# Support.net
KiCad netlist of a schematic drawn in Altium Designer
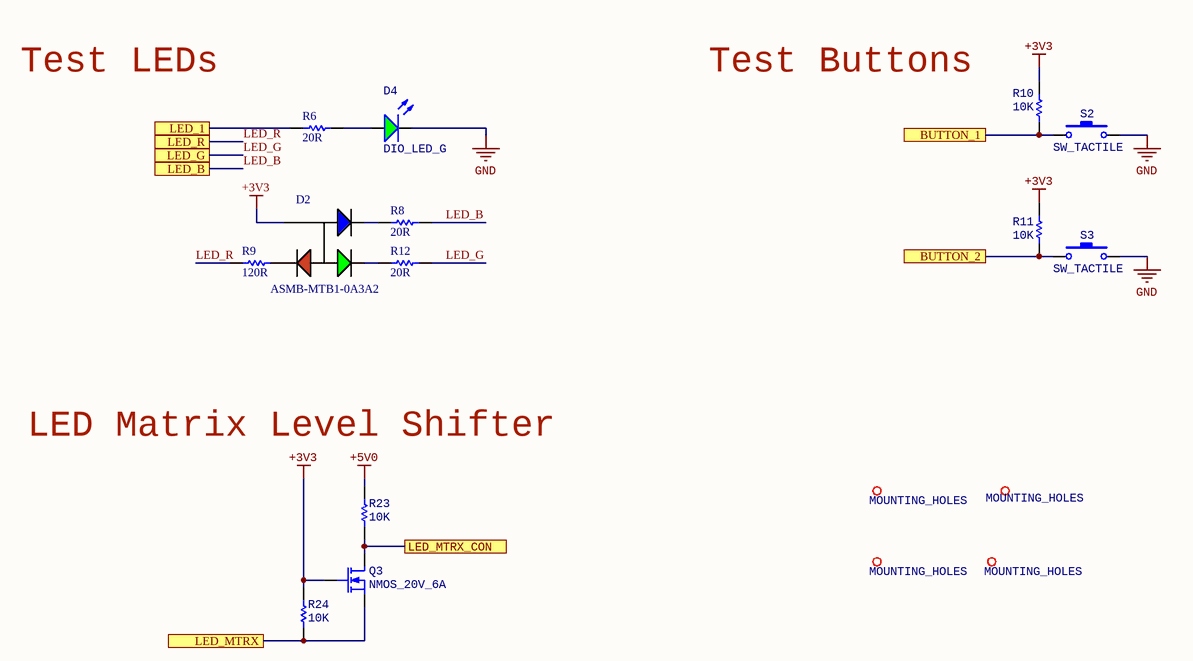
[diagram p0: Support.SchDoc]

(export (version "E")
  (design (tool "Eeschema 10.0.6"))
  (components
    (comp (ref "D2")
      (value "LED_RGB")
      (footprint "LED_RGB")
      (description "LED RGB DIFFUSED 4PLCC SMD")
      (fields (field (name "MANUFACTURER PART NUMBER 1") "ASMB-MTB1-0A3A2"))
      (libsource (lib "UWRT_Schematic_Library_2020") (part "LED_RGB"))
    )
    (comp (ref "D4")
      (value "DIO_LED_G")
      (footprint "LED_0805_LINE")
      (description "LED GREEN DIFFUSED 0805 SMD")
      (fields (field (name "MANUFACTURER") "OSRAM") (field (name "MPN") "LG R971-KN-1"))
      (libsource (lib "UWRT_Schematic_Library_2020") (part "DIO_LED_G"))
    )
    (comp (ref "MH1")
      (value "MOUNTING_HOLES")
      (footprint "MOUNTING_HOLE")
      (description "6cm x 6cm")
      (libsource (lib "UWRT_Schematic_Library_2020") (part "MOUNTING_HOLES"))
    )
    (comp (ref "MH2")
      (value "MOUNTING_HOLES")
      (footprint "MOUNTING_HOLE")
      (description "6cm x 6cm")
      (libsource (lib "UWRT_Schematic_Library_2020") (part "MOUNTING_HOLES"))
    )
    (comp (ref "MH3")
      (value "MOUNTING_HOLES")
      (footprint "MOUNTING_HOLE")
      (description "6cm x 6cm")
      (libsource (lib "UWRT_Schematic_Library_2020") (part "MOUNTING_HOLES"))
    )
    (comp (ref "MH4")
      (value "MOUNTING_HOLES")
      (footprint "MOUNTING_HOLE")
      (description "6cm x 6cm")
      (libsource (lib "UWRT_Schematic_Library_2020") (part "MOUNTING_HOLES"))
    )
    (comp (ref "Q3")
      (value "NMOS_20V_6A")
      (footprint "NMOS_SOT23-3")
      (description "MOSFET N-CH 20V 6A SOT23")
      (fields (field (name "MPN") "AO3420") (field (name "MANUFACTURER") "Alpha & Omega"))
      (libsource (lib "UWRT_Schematic_Library_2020") (part "NMOS_20V_6A"))
    )
    (comp (ref "R6")
      (value "20R")
      (footprint "RESC0603(1608)_N")
      (description "RES SMD 20 OHM 5% 1/10W 0603")
      (fields (field (name "MANUFACTURER") "Yageo") (field (name "MPN") "RC0603JR-0720RL"))
      (libsource (lib "UWRT_Schematic_Library_2020") (part "RES_20R_0603"))
    )
    (comp (ref "R8")
      (value "20R")
      (footprint "RESC0603(1608)_N")
      (description "RES SMD 20 OHM 5% 1/10W 0603")
      (fields (field (name "MANUFACTURER") "Yageo") (field (name "MPN") "RC0603JR-0720RL"))
      (libsource (lib "UWRT_Schematic_Library_2020") (part "RES_20R_0603"))
    )
    (comp (ref "R9")
      (value "120R")
      (footprint "RESC0603(1608)_N")
      (description "RES SMD 120 OHM 5% 1/10W 0603")
      (fields (field (name "MANUFACTURER") "Yageo") (field (name "MPN") "RC0603JR-07120RL"))
      (libsource (lib "UWRT_Schematic_Library_2020") (part "RES_120R_0603"))
    )
    (comp (ref "R10")
      (value "10K")
      (footprint "RESC0603(1608)_N")
      (description "RES SMD 10K OHM 5% 1/10W 0603")
      (fields (field (name "MANUFACTURER") "Yageo") (field (name "TOLERANCE") "5%"))
      (libsource (lib "UWRT_Schematic_Library_2020") (part "RES_10K_0603"))
    )
    (comp (ref "R11")
      (value "10K")
      (footprint "RESC0603(1608)_N")
      (description "RES SMD 10K OHM 5% 1/10W 0603")
      (fields (field (name "MANUFACTURER") "Yageo") (field (name "TOLERANCE") "5%"))
      (libsource (lib "UWRT_Schematic_Library_2020") (part "RES_10K_0603"))
    )
    (comp (ref "R12")
      (value "20R")
      (footprint "RESC0603(1608)_N")
      (description "RES SMD 20 OHM 5% 1/10W 0603")
      (fields (field (name "MANUFACTURER") "Yageo") (field (name "MPN") "RC0603JR-0720RL"))
      (libsource (lib "UWRT_Schematic_Library_2020") (part "RES_20R_0603"))
    )
    (comp (ref "R23")
      (value "10K")
      (footprint "RESC0603(1608)_N")
      (description "RES SMD 10K OHM 5% 1/10W 0603")
      (fields (field (name "MANUFACTURER") "Yageo") (field (name "MPN") "RC0603JR-0710KL"))
      (libsource (lib "UWRT_Schematic_Library_2020") (part "RES_10K_0603"))
    )
    (comp (ref "R24")
      (value "10K")
      (footprint "RESC0603(1608)_N")
      (description "RES SMD 10K OHM 5% 1/10W 0603")
      (fields (field (name "MANUFACTURER") "Yageo") (field (name "MPN") "RC0603JR-0710KL"))
      (libsource (lib "UWRT_Schematic_Library_2020") (part "RES_10K_0603"))
    )
    (comp (ref "S2")
      (value "SW_TACTILE")
      (footprint "B3U-1100P")
      (description "Tactile Switch (Grey)")
      (fields (field (name "MPN") "B3U-1100P") (field (name "MANUFACTURER") "Omron Electronics Inc-EMC Div"))
      (libsource (lib "UWRT_Schematic_Library_2020") (part "SW_TACTILE"))
    )
    (comp (ref "S3")
      (value "SW_TACTILE")
      (footprint "B3U-1100P")
      (description "Tactile Switch (Grey)")
      (fields (field (name "MPN") "B3U-1100P") (field (name "MANUFACTURER") "Omron Electronics Inc-EMC Div"))
      (libsource (lib "UWRT_Schematic_Library_2020") (part "SW_TACTILE"))
    )
  )
  (nets
    (net (code "1") (name "+3V3") (class "Default")
      (node (ref "D2") (pin "4") (pinfunction "9_4") (pintype "passive"))
      (node (ref "Q3") (pin "1") (pinfunction "G_1") (pintype "passive"))
      (node (ref "R10") (pin "1") (pinfunction "1_1") (pintype "passive"))
      (node (ref "R11") (pin "2") (pinfunction "2_2") (pintype "passive"))
      (node (ref "R24") (pin "1") (pinfunction "1_1") (pintype "passive"))
    )
    (net (code "2") (name "+5V0") (class "Default")
      (node (ref "R23") (pin "2") (pinfunction "2_2") (pintype "passive"))
    )
    (net (code "3") (name "/BUTTON_1") (class "Default")
      (node (ref "R10") (pin "2") (pinfunction "2_2") (pintype "passive"))
      (node (ref "S2") (pin "1") (pinfunction "1_1") (pintype "passive"))
    )
    (net (code "4") (name "/BUTTON_2") (class "Default")
      (node (ref "R11") (pin "1") (pinfunction "1_1") (pintype "passive"))
      (node (ref "S3") (pin "1") (pinfunction "1_1") (pintype "passive"))
    )
    (net (code "5") (name "/LED_1") (class "Default")
      (node (ref "R6") (pin "1") (pinfunction "1_1") (pintype "passive"))
    )
    (net (code "6") (name "/LED_B") (class "Default")
      (node (ref "R8") (pin "2") (pinfunction "2_2") (pintype "passive"))
    )
    (net (code "7") (name "/LED_G") (class "Default")
      (node (ref "R12") (pin "2") (pinfunction "2_2") (pintype "passive"))
    )
    (net (code "8") (name "/LED_MTRX") (class "Default")
      (node (ref "Q3") (pin "2") (pinfunction "S_2") (pintype "passive"))
      (node (ref "R24") (pin "2") (pinfunction "2_2") (pintype "passive"))
    )
    (net (code "9") (name "/LED_MTRX_CON") (class "Default")
      (node (ref "Q3") (pin "3") (pinfunction "D_3") (pintype "passive"))
      (node (ref "R23") (pin "1") (pinfunction "1_1") (pintype "passive"))
    )
    (net (code "10") (name "/LED_R") (class "Default")
      (node (ref "R9") (pin "1") (pinfunction "1_1") (pintype "passive"))
    )
    (net (code "11") (name "GND") (class "Default")
      (node (ref "D4") (pin "2") (pinfunction "K_2") (pintype "passive"))
      (node (ref "S2") (pin "2") (pinfunction "2_2") (pintype "passive"))
      (node (ref "S3") (pin "2") (pinfunction "2_2") (pintype "passive"))
    )
    (net (code "12") (name "Net-(D2-10)") (class "Default")
      (node (ref "D2") (pin "3") (pinfunction "10_3") (pintype "passive"))
      (node (ref "R8") (pin "1") (pinfunction "1_1") (pintype "passive"))
    )
    (net (code "13") (name "Net-(D2-11)") (class "Default")
      (node (ref "D2") (pin "1") (pinfunction "11_1") (pintype "passive"))
      (node (ref "R9") (pin "2") (pinfunction "2_2") (pintype "passive"))
    )
    (net (code "14") (name "Net-(D2-12)") (class "Default")
      (node (ref "D2") (pin "2") (pinfunction "12_2") (pintype "passive"))
      (node (ref "R12") (pin "1") (pinfunction "1_1") (pintype "passive"))
    )
    (net (code "15") (name "Net-(D4-A)") (class "Default")
      (node (ref "D4") (pin "1") (pinfunction "A_1") (pintype "passive"))
      (node (ref "R6") (pin "2") (pinfunction "2_2") (pintype "passive"))
    )
  )
)
